# Remote-control.net
KiCad netlist of a schematic drawn in Altium Designer
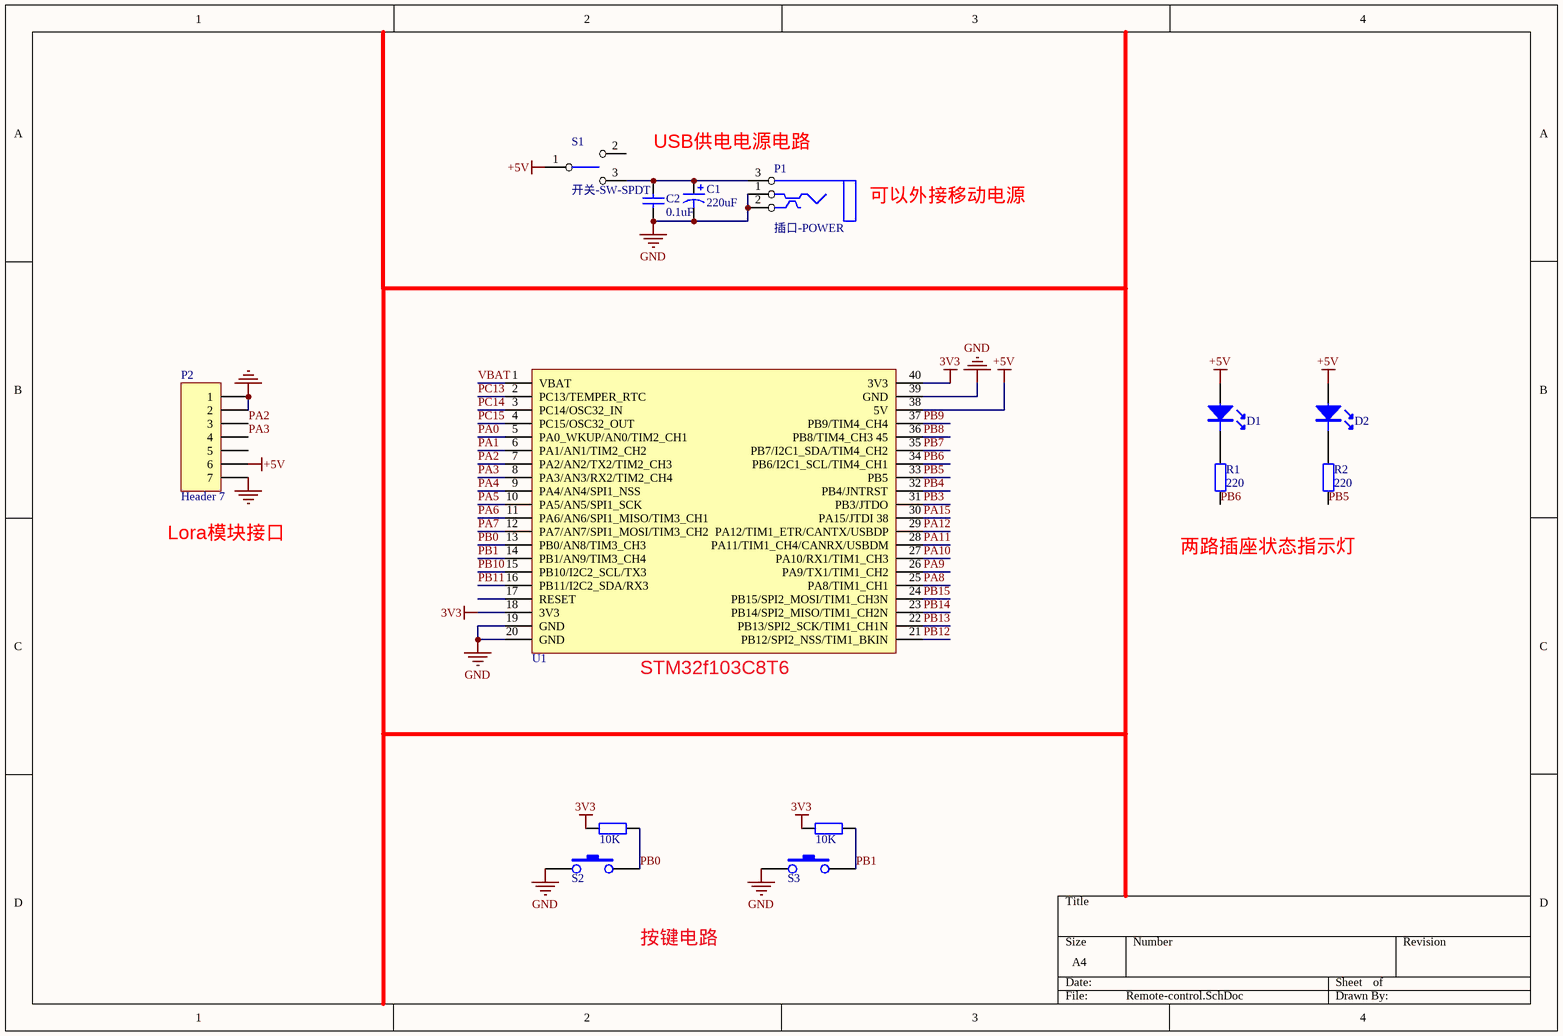
[diagram p0: Remote-control.SchDoc]

(export (version "E")
  (design (tool "Eeschema 10.0.6"))
  (components
    (comp (ref "C1")
      (value "220uF")
      (footprint "cd0.254")
      (description "Polarized Capacitor (Radial)")
      (fields (field (name "Comment") "Cap Pol1") (field (name "PUBLISHER") "Altium Limited"))
      (libsource (lib "Miscellaneous Devices") (part "Cap Pol1"))
    )
    (comp (ref "C2")
      (value "0.1uF")
      (footprint "cc0.254")
      (description "Capacitor")
      (fields (field (name "Comment") "Cap") (field (name "PUBLISHER") "Altium Limited"))
      (libsource (lib "Miscellaneous Devices") (part "Cap"))
    )
    (comp (ref "D1") (value "二极管--发光") (footprint "LED-5") (libsource (lib "买鹏飞的库") (part "二极管--发光")))
    (comp (ref "D2") (value "二极管--发光") (footprint "LED-5") (libsource (lib "买鹏飞的库") (part "二极管--发光")))
    (comp (ref "P1") (value "插口-POWER") (footprint "POW-DC") (libsource (lib "买鹏飞的库") (part "插口-POWER")))
    (comp (ref "P2")
      (value "Header 7")
      (footprint "PE32(433T20DC)")
      (description "Header, 7-Pin")
      (fields (field (name "PUBLISHER") "Altium Limited"))
      (libsource (lib "Miscellaneous Connectors") (part "Header 7"))
    )
    (comp (ref "R1")
      (value "220")
      (footprint "0805")
      (description "Resistor")
      (fields (field (name "Comment") "Res2") (field (name "PUBLISHER") "Altium Limited"))
      (libsource (lib "") (part "Res2_1"))
    )
    (comp (ref "R2")
      (value "220")
      (footprint "0805")
      (description "Resistor")
      (fields (field (name "Comment") "Res2") (field (name "PUBLISHER") "Altium Limited"))
      (libsource (lib "") (part "Res2_1"))
    )
    (comp (ref "R3")
      (value "10K")
      (footprint "AXIAL-0.4")
      (description "Resistor")
      (fields (field (name "Comment") "Res2") (field (name "PUBLISHER") "Altium Limited"))
      (libsource (lib "Miscellaneous Devices") (part "Res2"))
    )
    (comp (ref "R4")
      (value "10K")
      (footprint "AXIAL-0.4")
      (description "Resistor")
      (fields (field (name "Comment") "Res2") (field (name "PUBLISHER") "Altium Limited"))
      (libsource (lib "Miscellaneous Devices") (part "Res2"))
    )
    (comp (ref "S1") (value "开关-SW-SPDT") (footprint "SW3") (libsource (lib "买鹏飞的库") (part "开关-SW-SPDT")))
    (comp (ref "S2") (value "开关-微动") (footprint "sw4/6") (libsource (lib "买鹏飞的库") (part "开关-微动")))
    (comp (ref "S3") (value "开关-微动") (footprint "sw4/6") (libsource (lib "买鹏飞的库") (part "开关-微动")))
    (comp (ref "U1")
      (value "Core_STM32_YX")
      (footprint "Core_STM32_YX")
      (libsource (lib "买鹏飞的库") (part "Core_STM32_YX"))
    )
  )
  (nets
    (net (code "1") (name "+5V") (class "Default")
      (node (ref "D1") (pin "1") (pinfunction "1_1") (pintype "passive"))
      (node (ref "D2") (pin "1") (pinfunction "1_1") (pintype "passive"))
      (node (ref "P2") (pin "6") (pinfunction "6_6") (pintype "passive"))
      (node (ref "S1") (pin "1") (pinfunction "1_1") (pintype "passive"))
      (node (ref "U1") (pin "38") (pinfunction "5V_38") (pintype "passive"))
    )
    (net (code "2") (name "/PA0") (class "Default")
      (node (ref "U1") (pin "5") (pinfunction "PA0_WKUP/AN0/TIM2_CH1_5") (pintype "passive"))
    )
    (net (code "3") (name "/PA1") (class "Default")
      (node (ref "U1") (pin "6") (pinfunction "PA1/AN1/TIM2_CH2_6") (pintype "passive"))
    )
    (net (code "4") (name "/PA2") (class "Default")
      (node (ref "P2") (pin "3") (pinfunction "3_3") (pintype "passive"))
      (node (ref "U1") (pin "7") (pinfunction "PA2/AN2/TX2/TIM2_CH3_7") (pintype "passive"))
    )
    (net (code "5") (name "/PA3") (class "Default")
      (node (ref "P2") (pin "4") (pinfunction "4_4") (pintype "passive"))
      (node (ref "U1") (pin "8") (pinfunction "PA3/AN3/RX2/TIM2_CH4_8") (pintype "passive"))
    )
    (net (code "6") (name "/PA4") (class "Default")
      (node (ref "U1") (pin "9") (pinfunction "PA4/AN4/SPI1_NSS_9") (pintype "passive"))
    )
    (net (code "7") (name "/PA5") (class "Default")
      (node (ref "U1") (pin "10") (pinfunction "PA5/AN5/SPI1_SCK_10") (pintype "passive"))
    )
    (net (code "8") (name "/PA6") (class "Default")
      (node (ref "U1") (pin "11") (pinfunction "PA6/AN6/SPI1_MISO/TIM3_CH1_11") (pintype "passive"))
    )
    (net (code "9") (name "/PA7") (class "Default")
      (node (ref "U1") (pin "12") (pinfunction "PA7/AN7/SPI1_MOSI/TIM3_CH2_12") (pintype "passive"))
    )
    (net (code "10") (name "/PA8") (class "Default")
      (node (ref "U1") (pin "25") (pinfunction "PA8/TIM1_CH1_25") (pintype "passive"))
    )
    (net (code "11") (name "/PA9") (class "Default")
      (node (ref "U1") (pin "26") (pinfunction "PA9/TX1/TIM1_CH2_26") (pintype "passive"))
    )
    (net (code "12") (name "/PA10") (class "Default")
      (node (ref "U1") (pin "27") (pinfunction "PA10/RX1/TIM1_CH3_27") (pintype "passive"))
    )
    (net (code "13") (name "/PA11") (class "Default")
      (node (ref "U1") (pin "28") (pinfunction "PA11/TIM1_CH4/CANRX/USBDM_28") (pintype "passive"))
    )
    (net (code "14") (name "/PA12") (class "Default")
      (node (ref "U1") (pin "29") (pinfunction "PA12/TIM1_ETR/CANTX/USBDP_29") (pintype "passive"))
    )
    (net (code "15") (name "/PA15") (class "Default")
      (node (ref "U1") (pin "30") (pinfunction "PA15/JTDI_38_30") (pintype "passive"))
    )
    (net (code "16") (name "/PB0") (class "Default")
      (node (ref "R3") (pin "1") (pinfunction "1_1") (pintype "passive"))
      (node (ref "S2") (pin "2") (pinfunction "2_2") (pintype "passive"))
      (node (ref "U1") (pin "13") (pinfunction "PB0/AN8/TIM3_CH3_13") (pintype "passive"))
    )
    (net (code "17") (name "/PB1") (class "Default")
      (node (ref "R4") (pin "1") (pinfunction "1_1") (pintype "passive"))
      (node (ref "S3") (pin "2") (pinfunction "2_2") (pintype "passive"))
      (node (ref "U1") (pin "14") (pinfunction "PB1/AN9/TIM3_CH4_14") (pintype "passive"))
    )
    (net (code "18") (name "/PB3") (class "Default")
      (node (ref "U1") (pin "31") (pinfunction "PB3/JTDO_31") (pintype "passive"))
    )
    (net (code "19") (name "/PB4") (class "Default")
      (node (ref "U1") (pin "32") (pinfunction "PB4/JNTRST_32") (pintype "passive"))
    )
    (net (code "20") (name "/PB5") (class "Default")
      (node (ref "R2") (pin "2") (pinfunction "2_2") (pintype "passive"))
      (node (ref "U1") (pin "33") (pinfunction "PB5_33") (pintype "passive"))
    )
    (net (code "21") (name "/PB6") (class "Default")
      (node (ref "R1") (pin "2") (pinfunction "2_2") (pintype "passive"))
      (node (ref "U1") (pin "34") (pinfunction "PB6/I2C1_SCL/TIM4_CH1_34") (pintype "passive"))
    )
    (net (code "22") (name "/PB7") (class "Default")
      (node (ref "U1") (pin "35") (pinfunction "PB7/I2C1_SDA/TIM4_CH2_35") (pintype "passive"))
    )
    (net (code "23") (name "/PB8") (class "Default")
      (node (ref "U1") (pin "36") (pinfunction "PB8/TIM4_CH3_45_36") (pintype "passive"))
    )
    (net (code "24") (name "/PB9") (class "Default")
      (node (ref "U1") (pin "37") (pinfunction "PB9/TIM4_CH4_37") (pintype "passive"))
    )
    (net (code "25") (name "/PB10") (class "Default")
      (node (ref "U1") (pin "15") (pinfunction "PB10/I2C2_SCL/TX3_15") (pintype "passive"))
    )
    (net (code "26") (name "/PB11") (class "Default")
      (node (ref "U1") (pin "16") (pinfunction "PB11/I2C2_SDA/RX3_16") (pintype "passive"))
    )
    (net (code "27") (name "/PB12") (class "Default")
      (node (ref "U1") (pin "21") (pinfunction "PB12/SPI2_NSS/TIM1_BKIN_21") (pintype "passive"))
    )
    (net (code "28") (name "/PB13") (class "Default")
      (node (ref "U1") (pin "22") (pinfunction "PB13/SPI2_SCK/TIM1_CH1N_22") (pintype "passive"))
    )
    (net (code "29") (name "/PB14") (class "Default")
      (node (ref "U1") (pin "23") (pinfunction "PB14/SPI2_MISO/TIM1_CH2N_23") (pintype "passive"))
    )
    (net (code "30") (name "/PB15") (class "Default")
      (node (ref "U1") (pin "24") (pinfunction "PB15/SPI2_MOSI/TIM1_CH3N_24") (pintype "passive"))
    )
    (net (code "31") (name "/PC13") (class "Default")
      (node (ref "U1") (pin "2") (pinfunction "PC13/TEMPER_RTC_2") (pintype "passive"))
    )
    (net (code "32") (name "/PC14") (class "Default")
      (node (ref "U1") (pin "3") (pinfunction "PC14/OSC32_IN_3") (pintype "passive"))
    )
    (net (code "33") (name "/PC15") (class "Default")
      (node (ref "U1") (pin "4") (pinfunction "PC15/OSC32_OUT_4") (pintype "passive"))
    )
    (net (code "34") (name "/VBAT") (class "Default")
      (node (ref "U1") (pin "1") (pinfunction "VBAT_1") (pintype "passive"))
    )
    (net (code "35") (name "3V3") (class "Default")
      (node (ref "R3") (pin "2") (pinfunction "2_2") (pintype "passive"))
      (node (ref "R4") (pin "2") (pinfunction "2_2") (pintype "passive"))
      (node (ref "U1") (pin "18") (pinfunction "3V3_18") (pintype "passive"))
      (node (ref "U1") (pin "40") (pinfunction "3V3_40") (pintype "passive"))
    )
    (net (code "36") (name "GND") (class "Default")
      (node (ref "C1") (pin "2") (pinfunction "2_2") (pintype "passive"))
      (node (ref "C2") (pin "1") (pinfunction "1_1") (pintype "passive"))
      (node (ref "P1") (pin "1") (pinfunction "1_1") (pintype "passive"))
      (node (ref "P1") (pin "2") (pinfunction "2_2") (pintype "passive"))
      (node (ref "P2") (pin "1") (pinfunction "1_1") (pintype "passive"))
      (node (ref "P2") (pin "2") (pinfunction "2_2") (pintype "passive"))
      (node (ref "P2") (pin "7") (pinfunction "7_7") (pintype "passive"))
      (node (ref "S2") (pin "1") (pinfunction "1_1") (pintype "passive"))
      (node (ref "S3") (pin "1") (pinfunction "1_1") (pintype "passive"))
      (node (ref "U1") (pin "19") (pinfunction "GND_19") (pintype "passive"))
      (node (ref "U1") (pin "20") (pinfunction "GND_20") (pintype "passive"))
      (node (ref "U1") (pin "39") (pinfunction "GND_39") (pintype "passive"))
    )
    (net (code "37") (name "Net-(C1-Pad1)") (class "Default")
      (node (ref "C1") (pin "1") (pinfunction "1_1") (pintype "passive"))
      (node (ref "C2") (pin "2") (pinfunction "2_2") (pintype "passive"))
      (node (ref "P1") (pin "3") (pinfunction "3_3") (pintype "passive"))
      (node (ref "S1") (pin "3") (pinfunction "3_3") (pintype "passive"))
    )
    (net (code "38") (name "Net-(D1-Pad2)") (class "Default")
      (node (ref "D1") (pin "2") (pinfunction "2_2") (pintype "passive"))
      (node (ref "R1") (pin "1") (pinfunction "1_1") (pintype "passive"))
    )
    (net (code "39") (name "Net-(D2-Pad2)") (class "Default")
      (node (ref "D2") (pin "2") (pinfunction "2_2") (pintype "passive"))
      (node (ref "R2") (pin "1") (pinfunction "1_1") (pintype "passive"))
    )
    (net (code "40") (name "unconnected-(P2-Pad5)") (class "Default")
      (node (ref "P2") (pin "5") (pinfunction "5_5") (pintype "passive"))
    )
    (net (code "41") (name "unconnected-(S1-Pad2)") (class "Default")
      (node (ref "S1") (pin "2") (pinfunction "2_2") (pintype "passive"))
    )
    (net (code "42") (name "unconnected-(U1-RESET-Pad17)") (class "Default")
      (node (ref "U1") (pin "17") (pinfunction "RESET_17") (pintype "passive"))
    )
  )
)
